# ftdi2updi.net
KiCad netlist of a schematic drawn in EAGLE
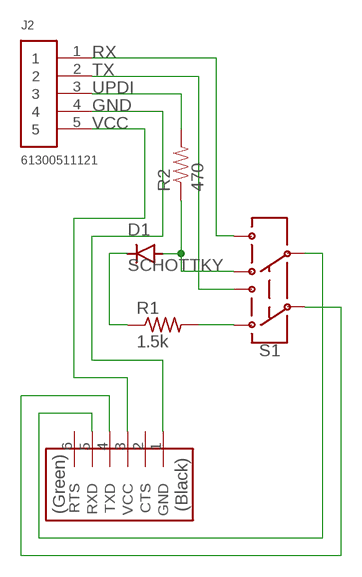
[diagram p0: schematic, sheet 1]

(export (version "E")
  (design (tool "Eeschema 10.0.6"))
  (components
    (comp (ref "D1")
      (value "SCHOTTKY")
      (footprint "eagle-import:MINI-SMA")
      (libsource (lib "eagle-import") (part "DIODE_SCHOTTKY_CDBM1100-G"))
    )
    (comp (ref "J2")
      (value "61300511121")
      (footprint "eagle-import:61300511121")
      (fields
        (field (name "DIGI_KEY_PART_NUMBER") "732-5318-ND")
        (field (name "MANUFACTURER") "Wurth Electronics Inc.")
        (field (name "CREATED_BY") "PCBLayout.com")
      )
      (libsource (lib "eagle-import") (part "61300511121"))
    )
    (comp (ref "R1")
      (value "1.5k")
      (footprint "eagle-import:R1206FAB")
      (libsource (lib "eagle-import") (part "R1206FAB"))
    )
    (comp (ref "R2")
      (value "470")
      (footprint "eagle-import:1206")
      (libsource (lib "eagle-import") (part "RESISTOR1206"))
    )
    (comp (ref "S1")
      (value "SWITCH-DPDT-SMD-AYZ0202")
      (footprint "eagle-import:SWITCH_DPDT_SMD_AYZ0202")
      (libsource (lib "eagle-import") (part "SWITCH-DPDT-SMD-AYZ0202"))
    )
    (comp (ref "U$1")
      (value "CONN_06_FTDI-SMD-HEADER")
      (footprint "eagle-import:1X06SMD")
      (libsource (lib "eagle-import") (part "CONN_06_FTDI-SMD-HEADER"))
    )
  )
  (nets
    (net (code "1") (name "/GND") (class "Default")
      (node (ref "J2") (pin "4") (pinfunction "4_4") (pintype "passive"))
      (node (ref "U$1") (pin "1") (pinfunction "GND_1") (pintype "bidirectional"))
    )
    (net (code "2") (name "/RX") (class "Default")
      (node (ref "J2") (pin "1") (pinfunction "1_1") (pintype "passive"))
      (node (ref "S1") (pin "4") (pinfunction "4_4") (pintype "bidirectional"))
    )
    (net (code "3") (name "/TX") (class "Default")
      (node (ref "J2") (pin "2") (pinfunction "2_2") (pintype "passive"))
      (node (ref "S1") (pin "1") (pinfunction "1_1") (pintype "bidirectional"))
    )
    (net (code "4") (name "/UPDI") (class "Default")
      (node (ref "J2") (pin "3") (pinfunction "3_3") (pintype "passive"))
      (node (ref "R2") (pin "2") (pinfunction "2_2") (pintype "passive"))
    )
    (net (code "5") (name "/VCC") (class "Default")
      (node (ref "J2") (pin "5") (pinfunction "5_5") (pintype "passive"))
      (node (ref "U$1") (pin "3") (pinfunction "VCC_3") (pintype "bidirectional"))
    )
    (net (code "6") (name "Net-(D1-PadANODE)") (class "Default")
      (node (ref "D1") (pin "ANODE") (pinfunction "ANODE_ANODE") (pintype "bidirectional"))
      (node (ref "R2") (pin "1") (pinfunction "1_1") (pintype "passive"))
      (node (ref "S1") (pin "6") (pinfunction "6_6") (pintype "bidirectional"))
    )
    (net (code "7") (name "Net-(D1-PadKATHODE)") (class "Default")
      (node (ref "D1") (pin "KATHODE") (pinfunction "KATHODE_KATHODE") (pintype "bidirectional"))
      (node (ref "R1") (pin "1") (pinfunction "1_1") (pintype "passive"))
    )
    (net (code "8") (name "Net-(R1-Pad2)") (class "Default")
      (node (ref "R1") (pin "2") (pinfunction "2_2") (pintype "passive"))
      (node (ref "S1") (pin "3") (pinfunction "3_3") (pintype "bidirectional"))
    )
    (net (code "9") (name "Net-(U$1-RXD)") (class "Default")
      (node (ref "S1") (pin "5") (pinfunction "5_5") (pintype "bidirectional"))
      (node (ref "U$1") (pin "5") (pinfunction "RXD_5") (pintype "bidirectional"))
    )
    (net (code "10") (name "Net-(U$1-TXD)") (class "Default")
      (node (ref "S1") (pin "2") (pinfunction "2_2") (pintype "bidirectional"))
      (node (ref "U$1") (pin "4") (pinfunction "TXD_4") (pintype "bidirectional"))
    )
    (net (code "11") (name "unconnected-(U$1-CTS-Pad2)") (class "Default")
      (node (ref "U$1") (pin "2") (pinfunction "CTS_2") (pintype "bidirectional"))
    )
    (net (code "12") (name "unconnected-(U$1-RTS-Pad6)") (class "Default")
      (node (ref "U$1") (pin "6") (pinfunction "RTS_6") (pintype "bidirectional"))
    )
  )
)
